# Chocolate_Vending_Machine_V1_0.net
KiCad netlist of a schematic drawn in Altium Designer
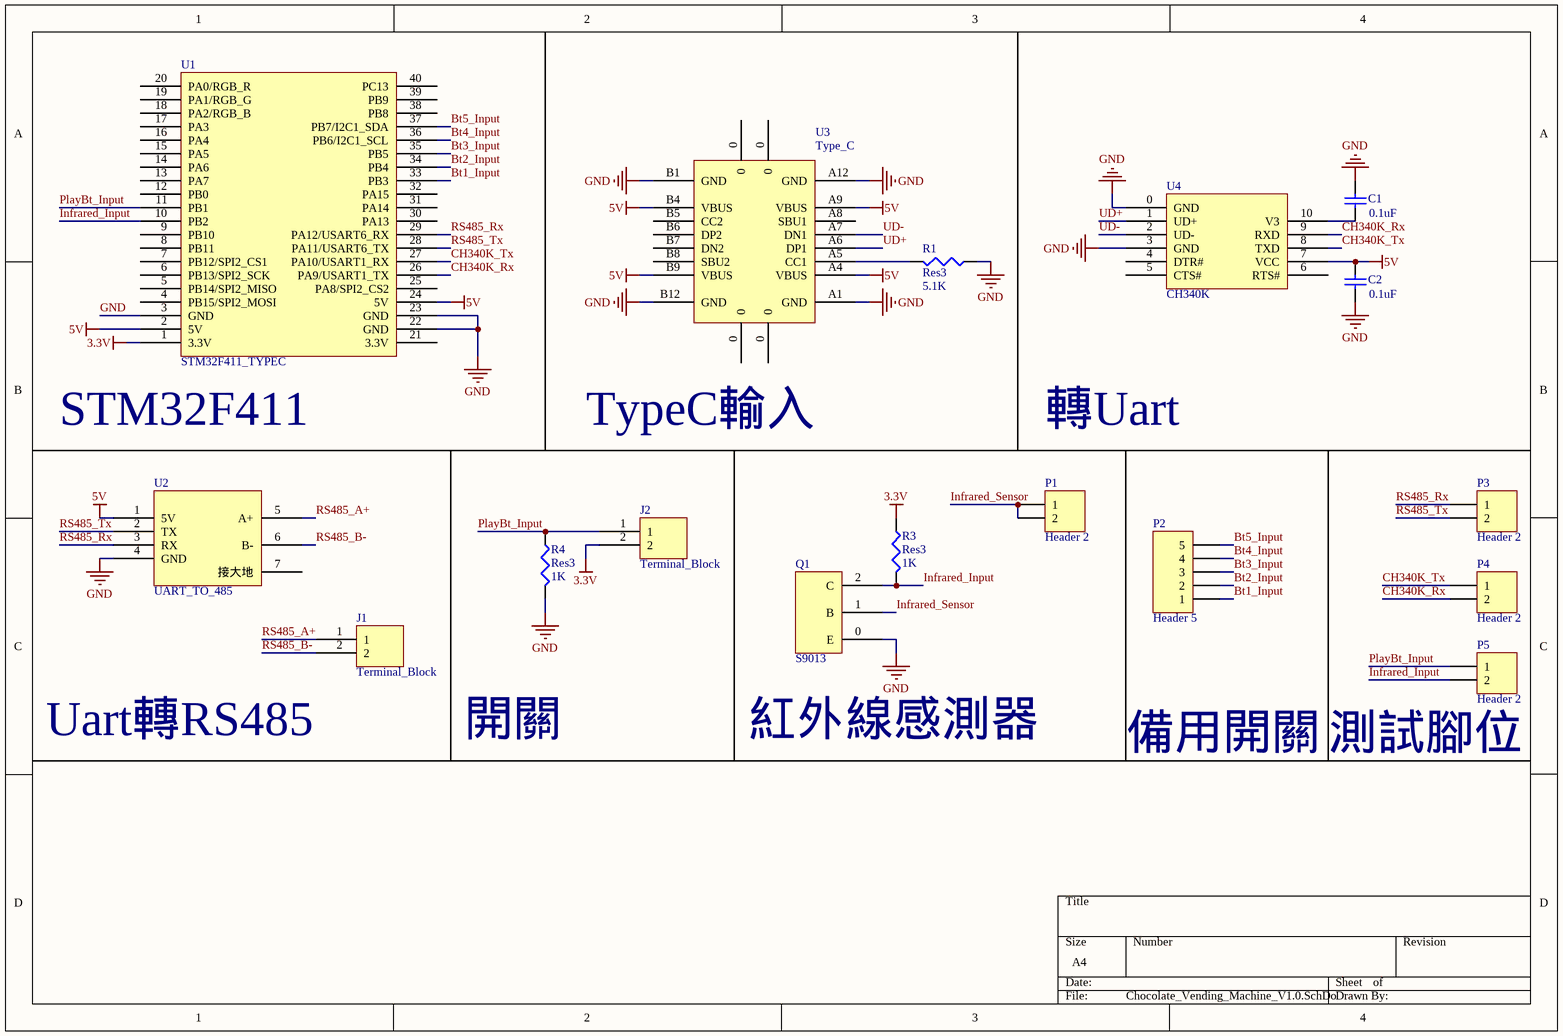
[diagram p0: Chocolate_Vending_Machine_V1.0.SchDoc]

(export (version "E")
  (design (tool "Eeschema 10.0.6"))
  (components
    (comp (ref "C1")
      (value "0.1uF")
      (footprint "1608[0603]")
      (description "Capacitor (Semiconductor SIM Model)")
      (fields (field (name "Comment") "Cap Semi") (field (name "PUBLISHER") "Altium Limited"))
      (libsource (lib "Miscellaneous Devices") (part "Cap Semi"))
    )
    (comp (ref "C2")
      (value "0.1uF")
      (footprint "1608[0603]")
      (description "Capacitor (Semiconductor SIM Model)")
      (fields (field (name "Comment") "Cap Semi") (field (name "PUBLISHER") "Altium Limited"))
      (libsource (lib "Miscellaneous Devices") (part "Cap Semi"))
    )
    (comp (ref "J1")
      (value "Terminal_Block")
      (footprint "terminal block")
      (libsource (lib "Lab_share") (part "Terminal Block"))
    )
    (comp (ref "J2")
      (value "Terminal_Block")
      (footprint "terminal block")
      (libsource (lib "Lab_share") (part "Terminal Block"))
    )
    (comp (ref "P1")
      (value "Header 2")
      (footprint "HDR1X2")
      (description "Header, 2-Pin")
      (fields (field (name "PUBLISHER") "Altium Limited"))
      (libsource (lib "Miscellaneous Connectors") (part "Header 2"))
    )
    (comp (ref "P2")
      (value "Header 5")
      (footprint "HDR1X5")
      (description "Header, 5-Pin")
      (fields (field (name "PUBLISHER") "Altium Limited"))
      (libsource (lib "Miscellaneous Connectors") (part "Header 5"))
    )
    (comp (ref "P3")
      (value "Header 2")
      (footprint "HDR1X2")
      (description "Header, 2-Pin")
      (fields (field (name "PUBLISHER") "Altium Limited"))
      (libsource (lib "Miscellaneous Connectors") (part "Header 2"))
    )
    (comp (ref "P4")
      (value "Header 2")
      (footprint "HDR1X2")
      (description "Header, 2-Pin")
      (fields (field (name "PUBLISHER") "Altium Limited"))
      (libsource (lib "Miscellaneous Connectors") (part "Header 2"))
    )
    (comp (ref "P5")
      (value "Header 2")
      (footprint "HDR1X2")
      (description "Header, 2-Pin")
      (fields (field (name "PUBLISHER") "Altium Limited"))
      (libsource (lib "Miscellaneous Connectors") (part "Header 2"))
    )
    (comp (ref "Q1") (value "S9013") (footprint "S9013") (libsource (lib "Lab_share") (part "S9013")))
    (comp (ref "R1")
      (value "Res3")
      (footprint "J1-0603")
      (description "Resistor")
      (fields (field (name "ALTIUM_VALUE") "5.1K") (field (name "PUBLISHER") "Altium Limited"))
      (libsource (lib "Miscellaneous Devices") (part "Res3"))
    )
    (comp (ref "R3")
      (value "Res3")
      (footprint "J1-0603")
      (description "Resistor")
      (fields (field (name "ALTIUM_VALUE") "1K") (field (name "PUBLISHER") "Altium Limited"))
      (libsource (lib "Miscellaneous Devices") (part "Res3"))
    )
    (comp (ref "R4")
      (value "Res3")
      (footprint "J1-0603")
      (description "Resistor")
      (fields (field (name "ALTIUM_VALUE") "1K") (field (name "PUBLISHER") "Altium Limited"))
      (libsource (lib "Miscellaneous Devices") (part "Res3"))
    )
    (comp (ref "U1")
      (value "STM32F411_TYPEC")
      (footprint "STM32F411_TypeC")
      (libsource (lib "Lab_share") (part "STM32F411_TYPEC"))
    )
    (comp (ref "U2")
      (value "UART_TO_485")
      (footprint "UART_TO_RS485")
      (libsource (lib "Lab_share") (part "UART_TO_485"))
    )
    (comp (ref "U3") (value "Type_C") (footprint "Type_C_V2") (libsource (lib "Lab_share") (part "Type_C")))
    (comp (ref "U4") (value "CH340K") (footprint "CH340K_V1") (libsource (lib "Lab_share") (part "CH340K")))
  )
  (nets
    (net (code "1") (name "/Bt1_Input") (class "Default")
      (node (ref "P2") (pin "1") (pinfunction "1_1") (pintype "passive"))
      (node (ref "U1") (pin "33") (pinfunction "PB3_33") (pintype "passive"))
    )
    (net (code "2") (name "/Bt2_Input") (class "Default")
      (node (ref "P2") (pin "2") (pinfunction "2_2") (pintype "passive"))
      (node (ref "U1") (pin "34") (pinfunction "PB4_34") (pintype "passive"))
    )
    (net (code "3") (name "/Bt3_Input") (class "Default")
      (node (ref "P2") (pin "3") (pinfunction "3_3") (pintype "passive"))
      (node (ref "U1") (pin "35") (pinfunction "PB5_35") (pintype "passive"))
    )
    (net (code "4") (name "/Bt4_Input") (class "Default")
      (node (ref "P2") (pin "4") (pinfunction "4_4") (pintype "passive"))
      (node (ref "U1") (pin "36") (pinfunction "PB6/I2C1_SCL_36") (pintype "passive"))
    )
    (net (code "5") (name "/Bt5_Input") (class "Default")
      (node (ref "P2") (pin "5") (pinfunction "5_5") (pintype "passive"))
      (node (ref "U1") (pin "37") (pinfunction "PB7/I2C1_SDA_37") (pintype "passive"))
    )
    (net (code "6") (name "/CH340K_Rx") (class "Default")
      (node (ref "P4") (pin "2") (pinfunction "2_2") (pintype "passive"))
      (node (ref "U1") (pin "26") (pinfunction "PA9/USART1_TX_26") (pintype "passive"))
      (node (ref "U4") (pin "9") (pinfunction "RXD_9") (pintype "passive"))
    )
    (net (code "7") (name "/CH340K_Tx") (class "Default")
      (node (ref "P4") (pin "1") (pinfunction "1_1") (pintype "passive"))
      (node (ref "U1") (pin "27") (pinfunction "PA10/USART1_RX_27") (pintype "passive"))
      (node (ref "U4") (pin "8") (pinfunction "TXD_8") (pintype "passive"))
    )
    (net (code "8") (name "/Infrared_Input") (class "Default")
      (node (ref "P5") (pin "2") (pinfunction "2_2") (pintype "passive"))
      (node (ref "Q1") (pin "2") (pinfunction "C_2") (pintype "passive"))
      (node (ref "R3") (pin "2") (pinfunction "2_2") (pintype "passive"))
      (node (ref "U1") (pin "10") (pinfunction "PB2_10") (pintype "passive"))
    )
    (net (code "9") (name "/Infrared_Sensor") (class "Default")
      (node (ref "P1") (pin "1") (pinfunction "1_1") (pintype "passive"))
      (node (ref "P1") (pin "2") (pinfunction "2_2") (pintype "passive"))
      (node (ref "Q1") (pin "1") (pinfunction "B_1") (pintype "passive"))
    )
    (net (code "10") (name "/PlayBt_Input") (class "Default")
      (node (ref "J2") (pin "1") (pinfunction "1_1") (pintype "passive"))
      (node (ref "P5") (pin "1") (pinfunction "1_1") (pintype "passive"))
      (node (ref "R4") (pin "1") (pinfunction "1_1") (pintype "passive"))
      (node (ref "U1") (pin "11") (pinfunction "PB1_11") (pintype "passive"))
    )
    (net (code "11") (name "/RS485_A+") (class "Default")
      (node (ref "J1") (pin "1") (pinfunction "1_1") (pintype "passive"))
      (node (ref "U2") (pin "5") (pinfunction "A+_5") (pintype "passive"))
    )
    (net (code "12") (name "/RS485_B-") (class "Default")
      (node (ref "J1") (pin "2") (pinfunction "2_2") (pintype "passive"))
      (node (ref "U2") (pin "6") (pinfunction "B-_6") (pintype "passive"))
    )
    (net (code "13") (name "/RS485_Rx") (class "Default")
      (node (ref "P3") (pin "1") (pinfunction "1_1") (pintype "passive"))
      (node (ref "U1") (pin "29") (pinfunction "PA12/USART6_RX_29") (pintype "passive"))
      (node (ref "U2") (pin "3") (pinfunction "RX_3") (pintype "passive"))
    )
    (net (code "14") (name "/RS485_Tx") (class "Default")
      (node (ref "P3") (pin "2") (pinfunction "2_2") (pintype "passive"))
      (node (ref "U1") (pin "28") (pinfunction "PA11/USART6_TX_28") (pintype "passive"))
      (node (ref "U2") (pin "2") (pinfunction "TX_2") (pintype "passive"))
    )
    (net (code "15") (name "/UD+") (class "Default")
      (node (ref "U3") (pin "A6") (pinfunction "DP1_A6") (pintype "passive"))
      (node (ref "U4") (pin "1") (pinfunction "UD+_1") (pintype "passive"))
    )
    (net (code "16") (name "/UD-") (class "Default")
      (node (ref "U3") (pin "A7") (pinfunction "DN1_A7") (pintype "passive"))
      (node (ref "U4") (pin "2") (pinfunction "UD-_2") (pintype "passive"))
    )
    (net (code "17") (name "3.3V") (class "Default")
      (node (ref "J2") (pin "2") (pinfunction "2_2") (pintype "passive"))
      (node (ref "R3") (pin "1") (pinfunction "1_1") (pintype "passive"))
      (node (ref "U1") (pin "1") (pinfunction "3.3V_1") (pintype "passive"))
    )
    (net (code "18") (name "5V") (class "Default")
      (node (ref "C2") (pin "2") (pinfunction "2_2") (pintype "passive"))
      (node (ref "U1") (pin "2") (pinfunction "5V_2") (pintype "passive"))
      (node (ref "U1") (pin "24") (pinfunction "5V_24") (pintype "passive"))
      (node (ref "U2") (pin "1") (pinfunction "5V_1") (pintype "passive"))
      (node (ref "U3") (pin "A4") (pinfunction "VBUS_A4") (pintype "passive"))
      (node (ref "U3") (pin "A9") (pinfunction "VBUS_A9") (pintype "passive"))
      (node (ref "U3") (pin "B4") (pinfunction "VBUS_B4") (pintype "passive"))
      (node (ref "U3") (pin "B9") (pinfunction "VBUS_B9") (pintype "passive"))
      (node (ref "U4") (pin "7") (pinfunction "VCC_7") (pintype "passive"))
    )
    (net (code "19") (name "GND") (class "Default")
      (node (ref "C1") (pin "2") (pinfunction "2_2") (pintype "passive"))
      (node (ref "C2") (pin "1") (pinfunction "1_1") (pintype "passive"))
      (node (ref "Q1") (pin "0") (pinfunction "E_0") (pintype "passive"))
      (node (ref "R1") (pin "1") (pinfunction "1_1") (pintype "passive"))
      (node (ref "R4") (pin "2") (pinfunction "2_2") (pintype "passive"))
      (node (ref "U1") (pin "22") (pinfunction "GND_22") (pintype "passive"))
      (node (ref "U1") (pin "23") (pinfunction "GND_23") (pintype "passive"))
      (node (ref "U1") (pin "3") (pinfunction "GND_3") (pintype "passive"))
      (node (ref "U2") (pin "4") (pinfunction "GND_4") (pintype "passive"))
      (node (ref "U3") (pin "A1") (pinfunction "GND_A1") (pintype "passive"))
      (node (ref "U3") (pin "A12") (pinfunction "GND_A12") (pintype "passive"))
      (node (ref "U3") (pin "B1") (pinfunction "GND_B1") (pintype "passive"))
      (node (ref "U3") (pin "B12") (pinfunction "GND_B12") (pintype "passive"))
      (node (ref "U4") (pin "0") (pinfunction "GND_0") (pintype "passive"))
      (node (ref "U4") (pin "3") (pinfunction "GND_3") (pintype "passive"))
    )
    (net (code "20") (name "Net-(U3-CC1)") (class "Default")
      (node (ref "R1") (pin "2") (pinfunction "2_2") (pintype "passive"))
      (node (ref "U3") (pin "A5") (pinfunction "CC1_A5") (pintype "passive"))
    )
    (net (code "21") (name "Net-(U4-V3)") (class "Default")
      (node (ref "C1") (pin "1") (pinfunction "1_1") (pintype "passive"))
      (node (ref "U4") (pin "10") (pinfunction "V3_10") (pintype "passive"))
    )
    (net (code "22") (name "unconnected-(U1-3.3V-Pad21)") (class "Default")
      (node (ref "U1") (pin "21") (pinfunction "3.3V_21") (pintype "passive"))
    )
    (net (code "23") (name "unconnected-(U1-PA0{slash}RGB_R-Pad20)") (class "Default")
      (node (ref "U1") (pin "20") (pinfunction "PA0/RGB_R_20") (pintype "passive"))
    )
    (net (code "24") (name "unconnected-(U1-PA1{slash}RGB_G-Pad19)") (class "Default")
      (node (ref "U1") (pin "19") (pinfunction "PA1/RGB_G_19") (pintype "passive"))
    )
    (net (code "25") (name "unconnected-(U1-PA2{slash}RGB_B-Pad18)") (class "Default")
      (node (ref "U1") (pin "18") (pinfunction "PA2/RGB_B_18") (pintype "passive"))
    )
    (net (code "26") (name "unconnected-(U1-PA3-Pad17)") (class "Default")
      (node (ref "U1") (pin "17") (pinfunction "PA3_17") (pintype "passive"))
    )
    (net (code "27") (name "unconnected-(U1-PA4-Pad16)") (class "Default")
      (node (ref "U1") (pin "16") (pinfunction "PA4_16") (pintype "passive"))
    )
    (net (code "28") (name "unconnected-(U1-PA5-Pad15)") (class "Default")
      (node (ref "U1") (pin "15") (pinfunction "PA5_15") (pintype "passive"))
    )
    (net (code "29") (name "unconnected-(U1-PA6-Pad14)") (class "Default")
      (node (ref "U1") (pin "14") (pinfunction "PA6_14") (pintype "passive"))
    )
    (net (code "30") (name "unconnected-(U1-PA7-Pad13)") (class "Default")
      (node (ref "U1") (pin "13") (pinfunction "PA7_13") (pintype "passive"))
    )
    (net (code "31") (name "unconnected-(U1-PA8{slash}SPI2_CS2-Pad25)") (class "Default")
      (node (ref "U1") (pin "25") (pinfunction "PA8/SPI2_CS2_25") (pintype "passive"))
    )
    (net (code "32") (name "unconnected-(U1-PA13-Pad30)") (class "Default")
      (node (ref "U1") (pin "30") (pinfunction "PA13_30") (pintype "passive"))
    )
    (net (code "33") (name "unconnected-(U1-PA14-Pad31)") (class "Default")
      (node (ref "U1") (pin "31") (pinfunction "PA14_31") (pintype "passive"))
    )
    (net (code "34") (name "unconnected-(U1-PA15-Pad32)") (class "Default")
      (node (ref "U1") (pin "32") (pinfunction "PA15_32") (pintype "passive"))
    )
    (net (code "35") (name "unconnected-(U1-PB0-Pad12)") (class "Default")
      (node (ref "U1") (pin "12") (pinfunction "PB0_12") (pintype "passive"))
    )
    (net (code "36") (name "unconnected-(U1-PB8-Pad38)") (class "Default")
      (node (ref "U1") (pin "38") (pinfunction "PB8_38") (pintype "passive"))
    )
    (net (code "37") (name "unconnected-(U1-PB9-Pad39)") (class "Default")
      (node (ref "U1") (pin "39") (pinfunction "PB9_39") (pintype "passive"))
    )
    (net (code "38") (name "unconnected-(U1-PB10-Pad9)") (class "Default")
      (node (ref "U1") (pin "9") (pinfunction "PB10_9") (pintype "passive"))
    )
    (net (code "39") (name "unconnected-(U1-PB11-Pad8)") (class "Default")
      (node (ref "U1") (pin "8") (pinfunction "PB11_8") (pintype "passive"))
    )
    (net (code "40") (name "unconnected-(U1-PB12{slash}SPI2_CS1-Pad7)") (class "Default")
      (node (ref "U1") (pin "7") (pinfunction "PB12/SPI2_CS1_7") (pintype "passive"))
    )
    (net (code "41") (name "unconnected-(U1-PB13{slash}SPI2_SCK-Pad6)") (class "Default")
      (node (ref "U1") (pin "6") (pinfunction "PB13/SPI2_SCK_6") (pintype "passive"))
    )
    (net (code "42") (name "unconnected-(U1-PB14{slash}SPI2_MISO-Pad5)") (class "Default")
      (node (ref "U1") (pin "5") (pinfunction "PB14/SPI2_MISO_5") (pintype "passive"))
    )
    (net (code "43") (name "unconnected-(U1-PB15{slash}SPI2_MOSI-Pad4)") (class "Default")
      (node (ref "U1") (pin "4") (pinfunction "PB15/SPI2_MOSI_4") (pintype "passive"))
    )
    (net (code "44") (name "unconnected-(U1-PC13-Pad40)") (class "Default")
      (node (ref "U1") (pin "40") (pinfunction "PC13_40") (pintype "passive"))
    )
    (net (code "45") (name "unconnected-(U2-接大地-Pad7)") (class "Default")
      (node (ref "U2") (pin "7") (pinfunction "接大地_7") (pintype "passive"))
    )
    (net (code "46") (name "unconnected-(U3-CC2-PadB5)") (class "Default")
      (node (ref "U3") (pin "B5") (pinfunction "CC2_B5") (pintype "passive"))
    )
    (net (code "47") (name "unconnected-(U3-DN2-PadB7)") (class "Default")
      (node (ref "U3") (pin "B7") (pinfunction "DN2_B7") (pintype "passive"))
    )
    (net (code "48") (name "unconnected-(U3-DP2-PadB6)") (class "Default")
      (node (ref "U3") (pin "B6") (pinfunction "DP2_B6") (pintype "passive"))
    )
    (net (code "49") (name "unconnected-(U3-Pad0)") (class "Default")
      (node (ref "U3") (pin "0") (pinfunction "0_0") (pintype "passive"))
    )
    (net (code "50") (name "unconnected-(U3-Pad0)_1") (class "Default")
      (node (ref "U3") (pin "0") (pinfunction "0_0") (pintype "passive"))
    )
    (net (code "51") (name "unconnected-(U3-Pad0)_2") (class "Default")
      (node (ref "U3") (pin "0") (pinfunction "0_0") (pintype "passive"))
    )
    (net (code "52") (name "unconnected-(U3-Pad0)_3") (class "Default")
      (node (ref "U3") (pin "0") (pinfunction "0_0") (pintype "passive"))
    )
    (net (code "53") (name "unconnected-(U3-SBU1-PadA8)") (class "Default")
      (node (ref "U3") (pin "A8") (pinfunction "SBU1_A8") (pintype "passive"))
    )
    (net (code "54") (name "unconnected-(U3-SBU2-PadB8)") (class "Default")
      (node (ref "U3") (pin "B8") (pinfunction "SBU2_B8") (pintype "passive"))
    )
    (net (code "55") (name "unconnected-(U4-CTS#-Pad5)") (class "Default")
      (node (ref "U4") (pin "5") (pinfunction "CTS#_5") (pintype "passive"))
    )
    (net (code "56") (name "unconnected-(U4-DTR#-Pad4)") (class "Default")
      (node (ref "U4") (pin "4") (pinfunction "DTR#_4") (pintype "passive"))
    )
    (net (code "57") (name "unconnected-(U4-RTS#-Pad6)") (class "Default")
      (node (ref "U4") (pin "6") (pinfunction "RTS#_6") (pintype "passive"))
    )
  )
)
